# HeartBlink.net
KiCad netlist of a schematic drawn in Altium Designer
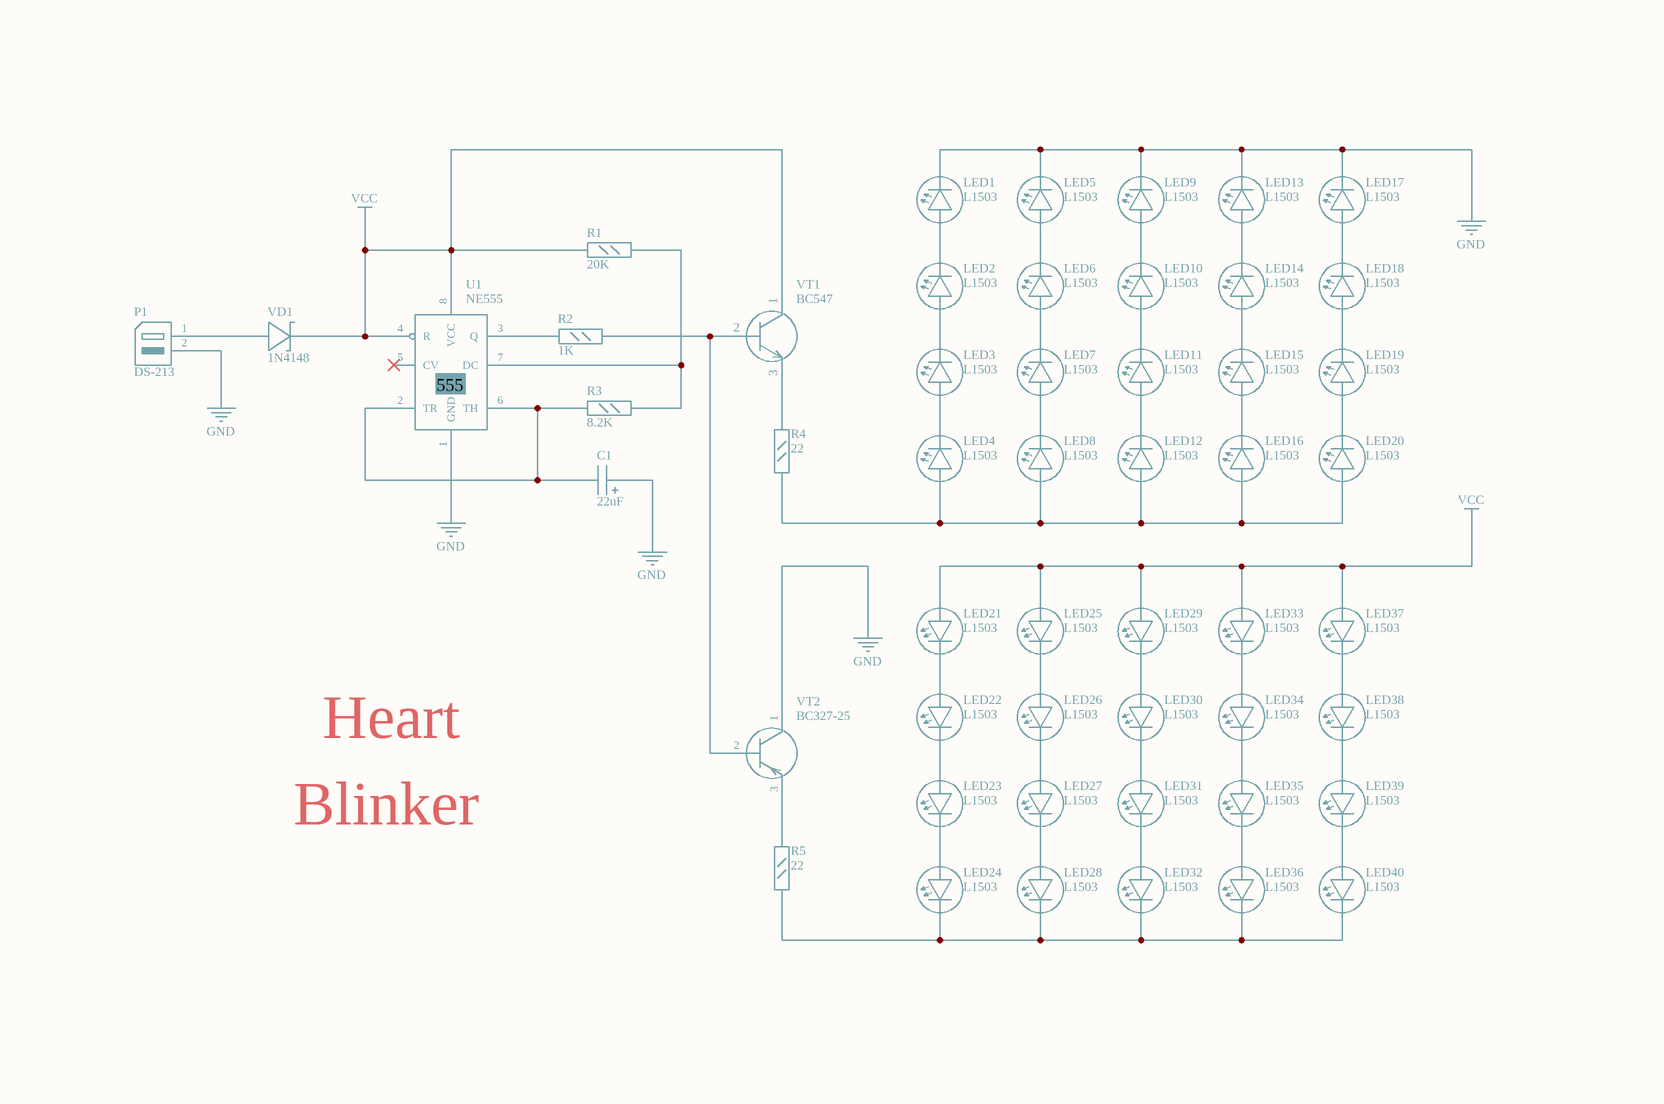
[diagram p0: HeartBlink.SchDoc]

(export (version "E")
  (design (tool "Eeschema 10.0.6"))
  (components
    (comp (ref "C1") (value "22uF") (footprint "CAP_POL5") (libsource (lib "CustomMillLib") (part "Cap_Pol")))
    (comp (ref "LED1")
      (value "L1503")
      (footprint "LED2.54-5MM-RED")
      (libsource (lib "Hi-Tech FireAlarm") (part "Led"))
    )
    (comp (ref "LED2")
      (value "L1503")
      (footprint "LED2.54-5MM-RED")
      (libsource (lib "Hi-Tech FireAlarm") (part "Led"))
    )
    (comp (ref "LED3")
      (value "L1503")
      (footprint "LED2.54-5MM-RED")
      (libsource (lib "Hi-Tech FireAlarm") (part "Led"))
    )
    (comp (ref "LED4")
      (value "L1503")
      (footprint "LED2.54-5MM-RED")
      (libsource (lib "Hi-Tech FireAlarm") (part "Led"))
    )
    (comp (ref "LED5")
      (value "L1503")
      (footprint "LED2.54-5MM-RED")
      (libsource (lib "Hi-Tech FireAlarm") (part "Led"))
    )
    (comp (ref "LED6")
      (value "L1503")
      (footprint "LED2.54-5MM-RED")
      (libsource (lib "Hi-Tech FireAlarm") (part "Led"))
    )
    (comp (ref "LED7")
      (value "L1503")
      (footprint "LED2.54-5MM-RED")
      (libsource (lib "Hi-Tech FireAlarm") (part "Led"))
    )
    (comp (ref "LED8")
      (value "L1503")
      (footprint "LED2.54-5MM-RED")
      (libsource (lib "Hi-Tech FireAlarm") (part "Led"))
    )
    (comp (ref "LED9")
      (value "L1503")
      (footprint "LED2.54-5MM-RED")
      (libsource (lib "Hi-Tech FireAlarm") (part "Led"))
    )
    (comp (ref "LED10")
      (value "L1503")
      (footprint "LED2.54-5MM-RED")
      (libsource (lib "Hi-Tech FireAlarm") (part "Led"))
    )
    (comp (ref "LED11")
      (value "L1503")
      (footprint "LED2.54-5MM-RED")
      (libsource (lib "Hi-Tech FireAlarm") (part "Led"))
    )
    (comp (ref "LED12")
      (value "L1503")
      (footprint "LED2.54-5MM-RED")
      (libsource (lib "Hi-Tech FireAlarm") (part "Led"))
    )
    (comp (ref "LED13")
      (value "L1503")
      (footprint "LED2.54-5MM-RED")
      (libsource (lib "Hi-Tech FireAlarm") (part "Led"))
    )
    (comp (ref "LED14")
      (value "L1503")
      (footprint "LED2.54-5MM-RED")
      (libsource (lib "Hi-Tech FireAlarm") (part "Led"))
    )
    (comp (ref "LED15")
      (value "L1503")
      (footprint "LED2.54-5MM-RED")
      (libsource (lib "Hi-Tech FireAlarm") (part "Led"))
    )
    (comp (ref "LED16")
      (value "L1503")
      (footprint "LED2.54-5MM-RED")
      (libsource (lib "Hi-Tech FireAlarm") (part "Led"))
    )
    (comp (ref "LED17")
      (value "L1503")
      (footprint "LED2.54-5MM-RED")
      (libsource (lib "Hi-Tech FireAlarm") (part "Led"))
    )
    (comp (ref "LED18")
      (value "L1503")
      (footprint "LED2.54-5MM-RED")
      (libsource (lib "Hi-Tech FireAlarm") (part "Led"))
    )
    (comp (ref "LED19")
      (value "L1503")
      (footprint "LED2.54-5MM-RED")
      (libsource (lib "Hi-Tech FireAlarm") (part "Led"))
    )
    (comp (ref "LED20")
      (value "L1503")
      (footprint "LED2.54-5MM-RED")
      (libsource (lib "Hi-Tech FireAlarm") (part "Led"))
    )
    (comp (ref "LED21")
      (value "L1503")
      (footprint "LED2.54-5MM-RED")
      (libsource (lib "Hi-Tech FireAlarm") (part "Led"))
    )
    (comp (ref "LED22")
      (value "L1503")
      (footprint "LED2.54-5MM-RED")
      (libsource (lib "Hi-Tech FireAlarm") (part "Led"))
    )
    (comp (ref "LED23")
      (value "L1503")
      (footprint "LED2.54-5MM-RED")
      (libsource (lib "Hi-Tech FireAlarm") (part "Led"))
    )
    (comp (ref "LED24")
      (value "L1503")
      (footprint "LED2.54-5MM-RED")
      (libsource (lib "Hi-Tech FireAlarm") (part "Led"))
    )
    (comp (ref "LED25")
      (value "L1503")
      (footprint "LED2.54-5MM-RED")
      (libsource (lib "Hi-Tech FireAlarm") (part "Led"))
    )
    (comp (ref "LED26")
      (value "L1503")
      (footprint "LED2.54-5MM-RED")
      (libsource (lib "Hi-Tech FireAlarm") (part "Led"))
    )
    (comp (ref "LED27")
      (value "L1503")
      (footprint "LED2.54-5MM-RED")
      (libsource (lib "Hi-Tech FireAlarm") (part "Led"))
    )
    (comp (ref "LED28")
      (value "L1503")
      (footprint "LED2.54-5MM-RED")
      (libsource (lib "Hi-Tech FireAlarm") (part "Led"))
    )
    (comp (ref "LED29")
      (value "L1503")
      (footprint "LED2.54-5MM-RED")
      (libsource (lib "Hi-Tech FireAlarm") (part "Led"))
    )
    (comp (ref "LED30")
      (value "L1503")
      (footprint "LED2.54-5MM-RED")
      (libsource (lib "Hi-Tech FireAlarm") (part "Led"))
    )
    (comp (ref "LED31")
      (value "L1503")
      (footprint "LED2.54-5MM-RED")
      (libsource (lib "Hi-Tech FireAlarm") (part "Led"))
    )
    (comp (ref "LED32")
      (value "L1503")
      (footprint "LED2.54-5MM-RED")
      (libsource (lib "Hi-Tech FireAlarm") (part "Led"))
    )
    (comp (ref "LED33")
      (value "L1503")
      (footprint "LED2.54-5MM-RED")
      (libsource (lib "Hi-Tech FireAlarm") (part "Led"))
    )
    (comp (ref "LED34")
      (value "L1503")
      (footprint "LED2.54-5MM-RED")
      (libsource (lib "Hi-Tech FireAlarm") (part "Led"))
    )
    (comp (ref "LED35")
      (value "L1503")
      (footprint "LED2.54-5MM-RED")
      (libsource (lib "Hi-Tech FireAlarm") (part "Led"))
    )
    (comp (ref "LED36")
      (value "L1503")
      (footprint "LED2.54-5MM-RED")
      (libsource (lib "Hi-Tech FireAlarm") (part "Led"))
    )
    (comp (ref "LED37")
      (value "L1503")
      (footprint "LED2.54-5MM-RED")
      (libsource (lib "Hi-Tech FireAlarm") (part "Led"))
    )
    (comp (ref "LED38")
      (value "L1503")
      (footprint "LED2.54-5MM-RED")
      (libsource (lib "Hi-Tech FireAlarm") (part "Led"))
    )
    (comp (ref "LED39")
      (value "L1503")
      (footprint "LED2.54-5MM-RED")
      (libsource (lib "Hi-Tech FireAlarm") (part "Led"))
    )
    (comp (ref "LED40")
      (value "L1503")
      (footprint "LED2.54-5MM-RED")
      (libsource (lib "Hi-Tech FireAlarm") (part "Led"))
    )
    (comp (ref "P1") (value "DS-213") (footprint "ST-213") (libsource (lib "Connectors") (part "CHOP2_P")))
    (comp (ref "R1") (value "20K") (footprint "AXIAL10R") (libsource (lib "CustomMillLib") (part "Res")))
    (comp (ref "R2") (value "1K") (footprint "AXIAL10R") (libsource (lib "Hi-Tech FireAlarm") (part "Res")))
    (comp (ref "R3") (value "8.2K") (footprint "AXIAL10R") (libsource (lib "CustomMillLib") (part "Res")))
    (comp (ref "R4") (value "22") (footprint "AXIAL10R") (libsource (lib "CustomMillLib") (part "Res")))
    (comp (ref "R5") (value "22") (footprint "AXIAL10R") (libsource (lib "Hi-Tech FireAlarm") (part "Res")))
    (comp (ref "U1") (value "NE555") (footprint "SOIC8") (libsource (lib "Hi-Tech FireAlarm") (part "NE555")))
    (comp (ref "VD1")
      (value "1N4148")
      (footprint "AXIAL10D-BL")
      (libsource (lib "CustomMillLib") (part "Diode_Sc"))
    )
    (comp (ref "VT1") (value "BC547") (footprint "TO-92") (libsource (lib "CustomMillLib") (part "NPN_CBE")))
    (comp (ref "VT2")
      (value "BC327-25")
      (footprint "TO-92")
      (libsource (lib "CustomMillLib") (part "PNP_CBE"))
    )
  )
  (nets
    (net (code "1") (name "GND") (class "Default")
      (node (ref "C1") (pin "1") (pinfunction "61_1") (pintype "passive"))
      (node (ref "LED1") (pin "2") (pinfunction "6_2") (pintype "passive"))
      (node (ref "LED13") (pin "2") (pinfunction "6_2") (pintype "passive"))
      (node (ref "LED17") (pin "2") (pinfunction "6_2") (pintype "passive"))
      (node (ref "LED5") (pin "2") (pinfunction "6_2") (pintype "passive"))
      (node (ref "LED9") (pin "2") (pinfunction "6_2") (pintype "passive"))
      (node (ref "P1") (pin "2") (pinfunction "2_2") (pintype "passive"))
      (node (ref "U1") (pin "1") (pinfunction "GND_1") (pintype "passive"))
      (node (ref "VT2") (pin "1") (pinfunction "9_1") (pintype "passive"))
    )
    (net (code "2") (name "Net-(C1-62)") (class "Default")
      (node (ref "C1") (pin "2") (pinfunction "62_2") (pintype "passive"))
      (node (ref "R3") (pin "2") (pinfunction "2_2") (pintype "passive"))
      (node (ref "U1") (pin "2") (pinfunction "TR_2") (pintype "passive"))
      (node (ref "U1") (pin "6") (pinfunction "TH_6") (pintype "passive"))
    )
    (net (code "3") (name "Net-(LED1-5)") (class "Default")
      (node (ref "LED1") (pin "1") (pinfunction "5_1") (pintype "passive"))
      (node (ref "LED2") (pin "2") (pinfunction "6_2") (pintype "passive"))
    )
    (net (code "4") (name "Net-(LED2-5)") (class "Default")
      (node (ref "LED2") (pin "1") (pinfunction "5_1") (pintype "passive"))
      (node (ref "LED3") (pin "2") (pinfunction "6_2") (pintype "passive"))
    )
    (net (code "5") (name "Net-(LED3-5)") (class "Default")
      (node (ref "LED3") (pin "1") (pinfunction "5_1") (pintype "passive"))
      (node (ref "LED4") (pin "2") (pinfunction "6_2") (pintype "passive"))
    )
    (net (code "6") (name "Net-(LED5-5)") (class "Default")
      (node (ref "LED5") (pin "1") (pinfunction "5_1") (pintype "passive"))
      (node (ref "LED6") (pin "2") (pinfunction "6_2") (pintype "passive"))
    )
    (net (code "7") (name "Net-(LED6-5)") (class "Default")
      (node (ref "LED6") (pin "1") (pinfunction "5_1") (pintype "passive"))
      (node (ref "LED7") (pin "2") (pinfunction "6_2") (pintype "passive"))
    )
    (net (code "8") (name "Net-(LED7-5)") (class "Default")
      (node (ref "LED7") (pin "1") (pinfunction "5_1") (pintype "passive"))
      (node (ref "LED8") (pin "2") (pinfunction "6_2") (pintype "passive"))
    )
    (net (code "9") (name "Net-(LED10-5)") (class "Default")
      (node (ref "LED10") (pin "1") (pinfunction "5_1") (pintype "passive"))
      (node (ref "LED11") (pin "2") (pinfunction "6_2") (pintype "passive"))
    )
    (net (code "10") (name "Net-(LED10-6)") (class "Default")
      (node (ref "LED10") (pin "2") (pinfunction "6_2") (pintype "passive"))
      (node (ref "LED9") (pin "1") (pinfunction "5_1") (pintype "passive"))
    )
    (net (code "11") (name "Net-(LED11-5)") (class "Default")
      (node (ref "LED11") (pin "1") (pinfunction "5_1") (pintype "passive"))
      (node (ref "LED12") (pin "2") (pinfunction "6_2") (pintype "passive"))
    )
    (net (code "12") (name "Net-(LED12-5)") (class "Default")
      (node (ref "LED12") (pin "1") (pinfunction "5_1") (pintype "passive"))
      (node (ref "LED16") (pin "1") (pinfunction "5_1") (pintype "passive"))
      (node (ref "LED20") (pin "1") (pinfunction "5_1") (pintype "passive"))
      (node (ref "LED4") (pin "1") (pinfunction "5_1") (pintype "passive"))
      (node (ref "LED8") (pin "1") (pinfunction "5_1") (pintype "passive"))
      (node (ref "R4") (pin "1") (pinfunction "2_1") (pintype "passive"))
    )
    (net (code "13") (name "Net-(LED13-5)") (class "Default")
      (node (ref "LED13") (pin "1") (pinfunction "5_1") (pintype "passive"))
      (node (ref "LED14") (pin "2") (pinfunction "6_2") (pintype "passive"))
    )
    (net (code "14") (name "Net-(LED14-5)") (class "Default")
      (node (ref "LED14") (pin "1") (pinfunction "5_1") (pintype "passive"))
      (node (ref "LED15") (pin "2") (pinfunction "6_2") (pintype "passive"))
    )
    (net (code "15") (name "Net-(LED15-5)") (class "Default")
      (node (ref "LED15") (pin "1") (pinfunction "5_1") (pintype "passive"))
      (node (ref "LED16") (pin "2") (pinfunction "6_2") (pintype "passive"))
    )
    (net (code "16") (name "Net-(LED17-5)") (class "Default")
      (node (ref "LED17") (pin "1") (pinfunction "5_1") (pintype "passive"))
      (node (ref "LED18") (pin "2") (pinfunction "6_2") (pintype "passive"))
    )
    (net (code "17") (name "Net-(LED18-5)") (class "Default")
      (node (ref "LED18") (pin "1") (pinfunction "5_1") (pintype "passive"))
      (node (ref "LED19") (pin "2") (pinfunction "6_2") (pintype "passive"))
    )
    (net (code "18") (name "Net-(LED19-5)") (class "Default")
      (node (ref "LED19") (pin "1") (pinfunction "5_1") (pintype "passive"))
      (node (ref "LED20") (pin "2") (pinfunction "6_2") (pintype "passive"))
    )
    (net (code "19") (name "Net-(LED21-6)") (class "Default")
      (node (ref "LED21") (pin "2") (pinfunction "6_2") (pintype "passive"))
      (node (ref "LED22") (pin "1") (pinfunction "5_1") (pintype "passive"))
    )
    (net (code "20") (name "Net-(LED22-6)") (class "Default")
      (node (ref "LED22") (pin "2") (pinfunction "6_2") (pintype "passive"))
      (node (ref "LED23") (pin "1") (pinfunction "5_1") (pintype "passive"))
    )
    (net (code "21") (name "Net-(LED23-6)") (class "Default")
      (node (ref "LED23") (pin "2") (pinfunction "6_2") (pintype "passive"))
      (node (ref "LED24") (pin "1") (pinfunction "5_1") (pintype "passive"))
    )
    (net (code "22") (name "Net-(LED24-6)") (class "Default")
      (node (ref "LED24") (pin "2") (pinfunction "6_2") (pintype "passive"))
      (node (ref "LED28") (pin "2") (pinfunction "6_2") (pintype "passive"))
      (node (ref "LED32") (pin "2") (pinfunction "6_2") (pintype "passive"))
      (node (ref "LED36") (pin "2") (pinfunction "6_2") (pintype "passive"))
      (node (ref "LED40") (pin "2") (pinfunction "6_2") (pintype "passive"))
      (node (ref "R5") (pin "1") (pinfunction "2_1") (pintype "passive"))
    )
    (net (code "23") (name "Net-(LED25-6)") (class "Default")
      (node (ref "LED25") (pin "2") (pinfunction "6_2") (pintype "passive"))
      (node (ref "LED26") (pin "1") (pinfunction "5_1") (pintype "passive"))
    )
    (net (code "24") (name "Net-(LED26-6)") (class "Default")
      (node (ref "LED26") (pin "2") (pinfunction "6_2") (pintype "passive"))
      (node (ref "LED27") (pin "1") (pinfunction "5_1") (pintype "passive"))
    )
    (net (code "25") (name "Net-(LED27-6)") (class "Default")
      (node (ref "LED27") (pin "2") (pinfunction "6_2") (pintype "passive"))
      (node (ref "LED28") (pin "1") (pinfunction "5_1") (pintype "passive"))
    )
    (net (code "26") (name "Net-(LED29-6)") (class "Default")
      (node (ref "LED29") (pin "2") (pinfunction "6_2") (pintype "passive"))
      (node (ref "LED30") (pin "1") (pinfunction "5_1") (pintype "passive"))
    )
    (net (code "27") (name "Net-(LED30-6)") (class "Default")
      (node (ref "LED30") (pin "2") (pinfunction "6_2") (pintype "passive"))
      (node (ref "LED31") (pin "1") (pinfunction "5_1") (pintype "passive"))
    )
    (net (code "28") (name "Net-(LED31-6)") (class "Default")
      (node (ref "LED31") (pin "2") (pinfunction "6_2") (pintype "passive"))
      (node (ref "LED32") (pin "1") (pinfunction "5_1") (pintype "passive"))
    )
    (net (code "29") (name "Net-(LED33-6)") (class "Default")
      (node (ref "LED33") (pin "2") (pinfunction "6_2") (pintype "passive"))
      (node (ref "LED34") (pin "1") (pinfunction "5_1") (pintype "passive"))
    )
    (net (code "30") (name "Net-(LED34-6)") (class "Default")
      (node (ref "LED34") (pin "2") (pinfunction "6_2") (pintype "passive"))
      (node (ref "LED35") (pin "1") (pinfunction "5_1") (pintype "passive"))
    )
    (net (code "31") (name "Net-(LED35-6)") (class "Default")
      (node (ref "LED35") (pin "2") (pinfunction "6_2") (pintype "passive"))
      (node (ref "LED36") (pin "1") (pinfunction "5_1") (pintype "passive"))
    )
    (net (code "32") (name "Net-(LED37-6)") (class "Default")
      (node (ref "LED37") (pin "2") (pinfunction "6_2") (pintype "passive"))
      (node (ref "LED38") (pin "1") (pinfunction "5_1") (pintype "passive"))
    )
    (net (code "33") (name "Net-(LED38-6)") (class "Default")
      (node (ref "LED38") (pin "2") (pinfunction "6_2") (pintype "passive"))
      (node (ref "LED39") (pin "1") (pinfunction "5_1") (pintype "passive"))
    )
    (net (code "34") (name "Net-(LED39-6)") (class "Default")
      (node (ref "LED39") (pin "2") (pinfunction "6_2") (pintype "passive"))
      (node (ref "LED40") (pin "1") (pinfunction "5_1") (pintype "passive"))
    )
    (net (code "35") (name "Net-(U1-DC)") (class "Default")
      (node (ref "R1") (pin "1") (pinfunction "2_1") (pintype "passive"))
      (node (ref "R3") (pin "1") (pinfunction "2_1") (pintype "passive"))
      (node (ref "U1") (pin "7") (pinfunction "DC_7") (pintype "passive"))
    )
    (net (code "36") (name "Net-(U1-Q)") (class "Default")
      (node (ref "R2") (pin "1") (pinfunction "2_1") (pintype "passive"))
      (node (ref "U1") (pin "3") (pinfunction "Q_3") (pintype "passive"))
    )
    (net (code "37") (name "Net-(VD1-63)") (class "Default")
      (node (ref "P1") (pin "1") (pinfunction "1_1") (pintype "passive"))
      (node (ref "VD1") (pin "1") (pinfunction "63_1") (pintype "passive"))
    )
    (net (code "38") (name "Net-(VT1-10)") (class "Default")
      (node (ref "R2") (pin "2") (pinfunction "2_2") (pintype "passive"))
      (node (ref "VT1") (pin "2") (pinfunction "10_2") (pintype "passive"))
      (node (ref "VT2") (pin "2") (pinfunction "10_2") (pintype "passive"))
    )
    (net (code "39") (name "Net-(VT1-11)") (class "Default")
      (node (ref "R4") (pin "2") (pinfunction "2_2") (pintype "passive"))
      (node (ref "VT1") (pin "3") (pinfunction "11_3") (pintype "passive"))
    )
    (net (code "40") (name "Net-(VT2-11)") (class "Default")
      (node (ref "R5") (pin "2") (pinfunction "2_2") (pintype "passive"))
      (node (ref "VT2") (pin "3") (pinfunction "11_3") (pintype "passive"))
    )
    (net (code "41") (name "VCC") (class "Default")
      (node (ref "LED21") (pin "1") (pinfunction "5_1") (pintype "passive"))
      (node (ref "LED25") (pin "1") (pinfunction "5_1") (pintype "passive"))
      (node (ref "LED29") (pin "1") (pinfunction "5_1") (pintype "passive"))
      (node (ref "LED33") (pin "1") (pinfunction "5_1") (pintype "passive"))
      (node (ref "LED37") (pin "1") (pinfunction "5_1") (pintype "passive"))
      (node (ref "R1") (pin "2") (pinfunction "2_2") (pintype "passive"))
      (node (ref "U1") (pin "4") (pinfunction "R_4") (pintype "passive"))
      (node (ref "U1") (pin "8") (pinfunction "VCC_8") (pintype "passive"))
      (node (ref "VD1") (pin "2") (pinfunction "64_2") (pintype "passive"))
      (node (ref "VT1") (pin "1") (pinfunction "9_1") (pintype "passive"))
    )
    (net (code "42") (name "unconnected-(U1-CV-Pad5)") (class "Default")
      (node (ref "U1") (pin "5") (pinfunction "CV_5") (pintype "passive+no_connect"))
    )
  )
)
